# BPW5046-RGB-LED-Panel.net
KiCad netlist of a schematic drawn in EAGLE
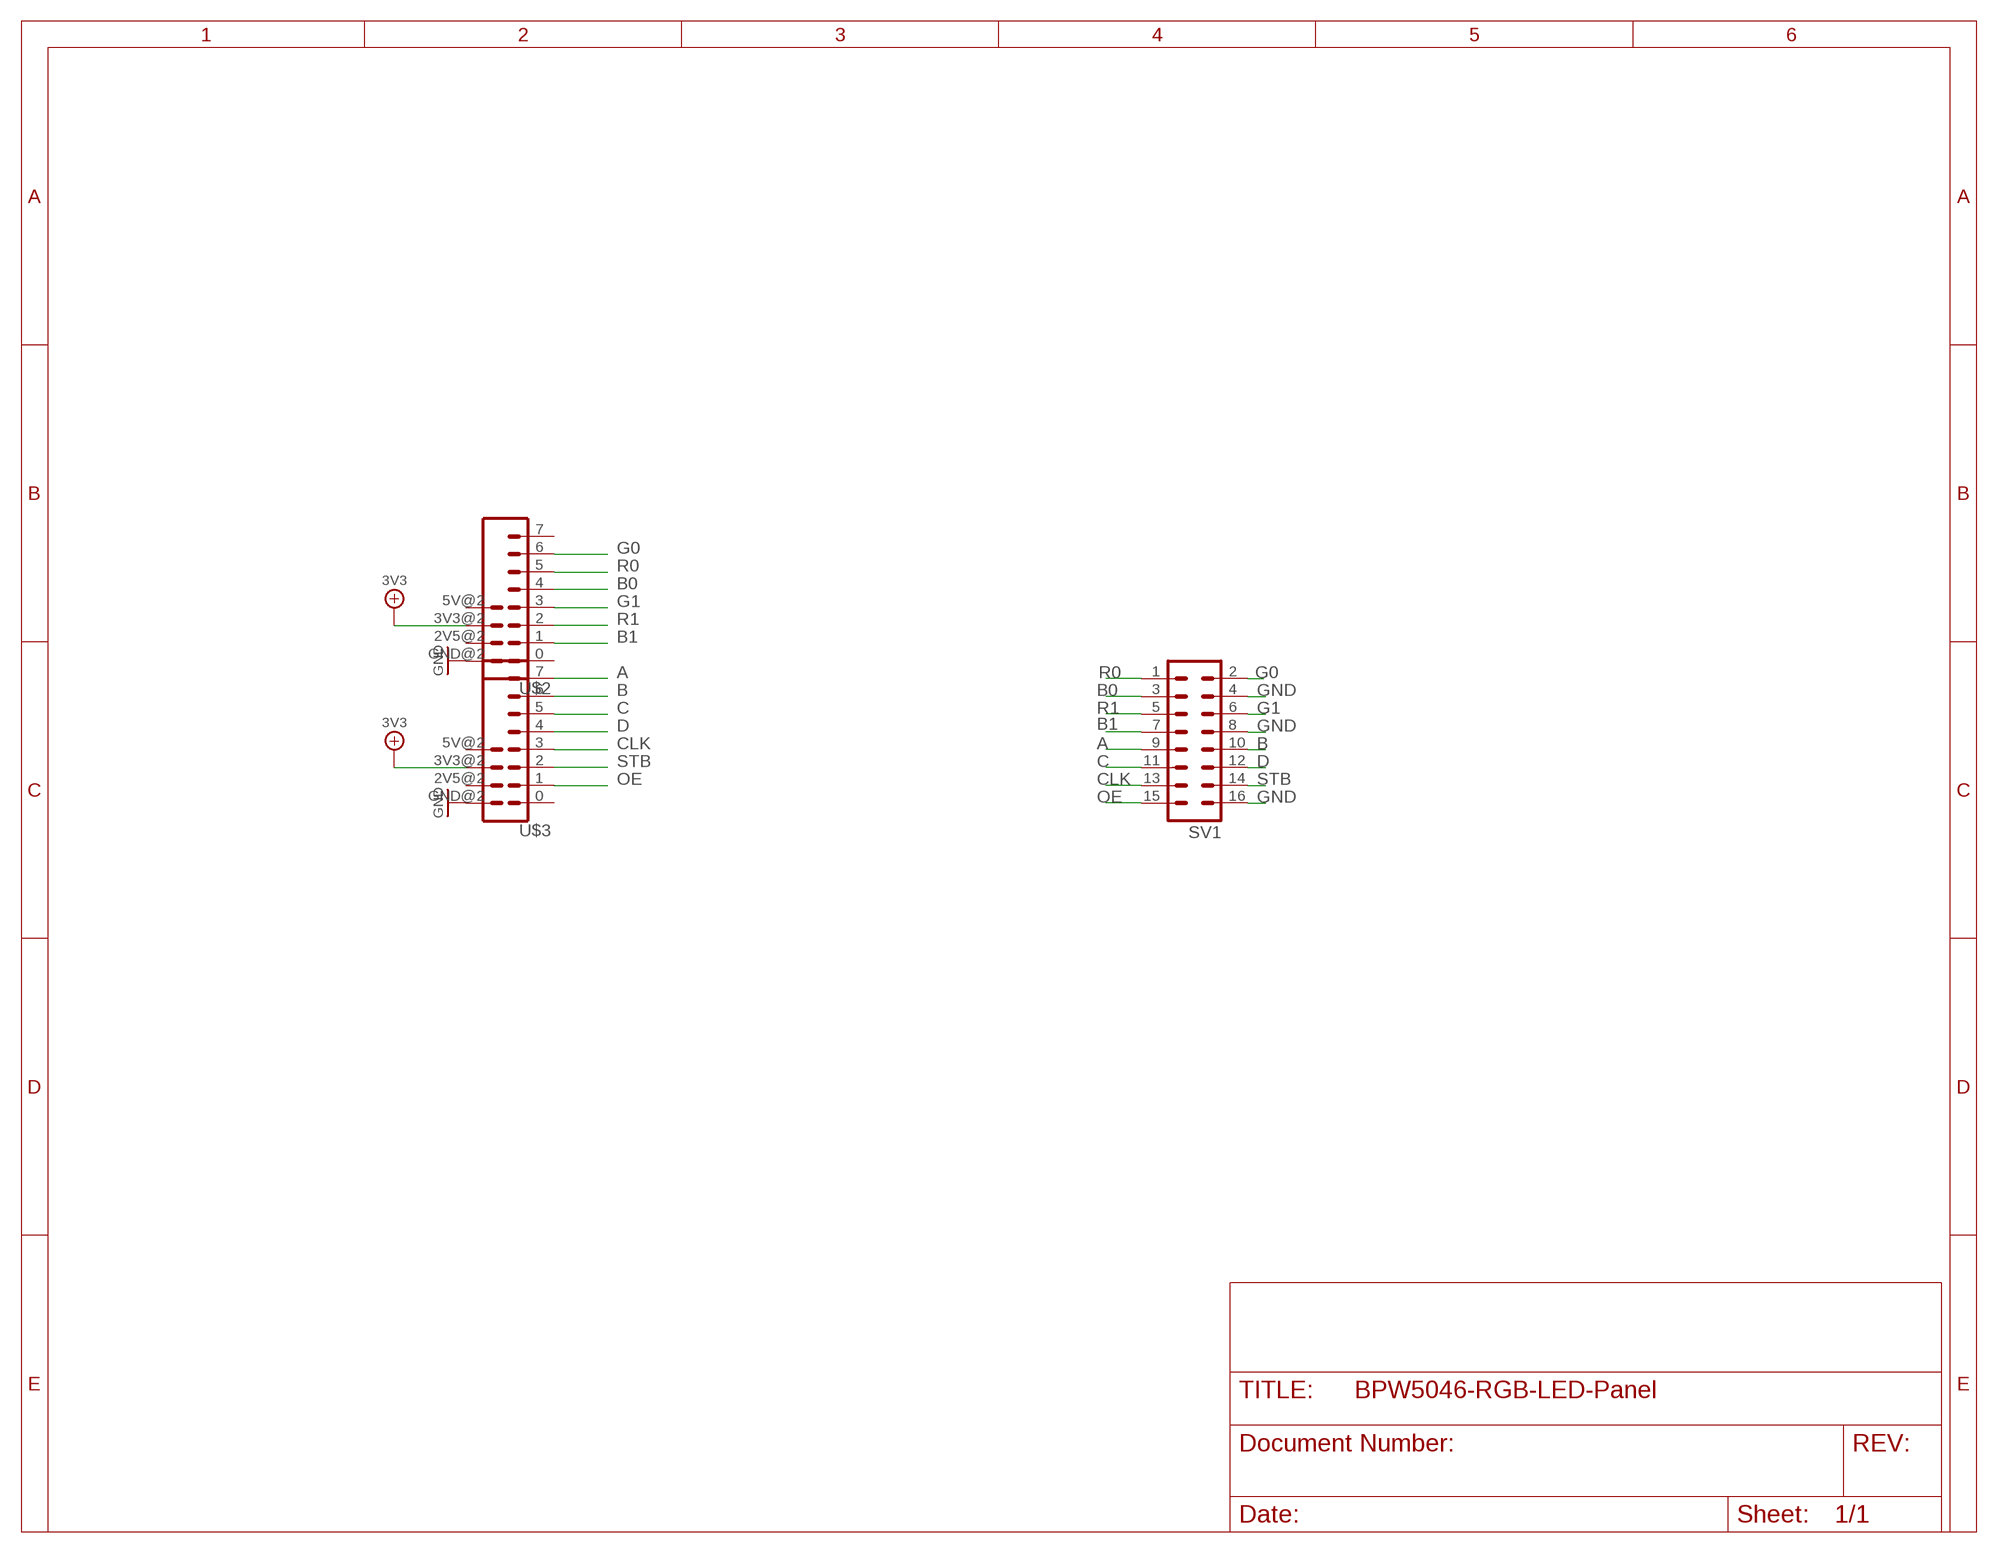
[diagram p0: schematic, sheet 1]

(export (version "E")
  (design (tool "Eeschema 10.0.6"))
  (components
    (comp (ref "SV1")
      (value "ML16")
      (footprint "eagle-import:ML16")
      (fields (field (name "PARTNO") "PRPC004DAAN-RC"))
      (libsource (lib "eagle-import") (part "ML16"))
    )
    (comp (ref "U$2")
      (value "WING8WING8_NOHOLES")
      (footprint "eagle-import:WINGSIDE_8BIT_NOHOLES")
      (fields (field (name "PARTNO") "68001-112HLF"))
      (libsource (lib "eagle-import") (part "WING8WING8_NOHOLES"))
    )
    (comp (ref "U$3")
      (value "WING8WING8_NOHOLES")
      (footprint "eagle-import:WINGSIDE_8BIT_NOHOLES")
      (fields (field (name "PARTNO") "68001-112HLF"))
      (libsource (lib "eagle-import") (part "WING8WING8_NOHOLES"))
    )
  )
  (nets
    (net (code "1") (name "/A") (class "Default")
      (node (ref "SV1") (pin "9") (pinfunction "9_9") (pintype "passive"))
      (node (ref "U$3") (pin "7") (pinfunction "8_7") (pintype "passive"))
    )
    (net (code "2") (name "/B") (class "Default")
      (node (ref "SV1") (pin "10") (pinfunction "10_10") (pintype "passive"))
      (node (ref "U$3") (pin "6") (pinfunction "7_6") (pintype "passive"))
    )
    (net (code "3") (name "/B0") (class "Default")
      (node (ref "SV1") (pin "3") (pinfunction "3_3") (pintype "passive"))
      (node (ref "U$2") (pin "4") (pinfunction "5_4") (pintype "passive"))
    )
    (net (code "4") (name "/B1") (class "Default")
      (node (ref "SV1") (pin "7") (pinfunction "7_7") (pintype "passive"))
      (node (ref "U$2") (pin "1") (pinfunction "2_1") (pintype "passive"))
    )
    (net (code "5") (name "/C") (class "Default")
      (node (ref "SV1") (pin "11") (pinfunction "11_11") (pintype "passive"))
      (node (ref "U$3") (pin "5") (pinfunction "6_5") (pintype "passive"))
    )
    (net (code "6") (name "/CLK") (class "Default")
      (node (ref "SV1") (pin "13") (pinfunction "13_13") (pintype "passive"))
      (node (ref "U$3") (pin "3") (pinfunction "4_3") (pintype "passive"))
    )
    (net (code "7") (name "/D") (class "Default")
      (node (ref "SV1") (pin "12") (pinfunction "12_12") (pintype "passive"))
      (node (ref "U$3") (pin "4") (pinfunction "5_4") (pintype "passive"))
    )
    (net (code "8") (name "/G0") (class "Default")
      (node (ref "SV1") (pin "2") (pinfunction "2_2") (pintype "passive"))
      (node (ref "U$2") (pin "6") (pinfunction "7_6") (pintype "passive"))
    )
    (net (code "9") (name "/G1") (class "Default")
      (node (ref "SV1") (pin "6") (pinfunction "6_6") (pintype "passive"))
      (node (ref "U$2") (pin "3") (pinfunction "4_3") (pintype "passive"))
    )
    (net (code "10") (name "/OE") (class "Default")
      (node (ref "SV1") (pin "15") (pinfunction "15_15") (pintype "passive"))
      (node (ref "U$3") (pin "1") (pinfunction "2_1") (pintype "passive"))
    )
    (net (code "11") (name "/R0") (class "Default")
      (node (ref "SV1") (pin "1") (pinfunction "1_1") (pintype "passive"))
      (node (ref "U$2") (pin "5") (pinfunction "6_5") (pintype "passive"))
    )
    (net (code "12") (name "/R1") (class "Default")
      (node (ref "SV1") (pin "5") (pinfunction "5_5") (pintype "passive"))
      (node (ref "U$2") (pin "2") (pinfunction "3_2") (pintype "passive"))
    )
    (net (code "13") (name "/STB") (class "Default")
      (node (ref "SV1") (pin "14") (pinfunction "14_14") (pintype "passive"))
      (node (ref "U$3") (pin "2") (pinfunction "3_2") (pintype "passive"))
    )
    (net (code "14") (name "3V3") (class "Default")
      (node (ref "U$2") (pin "3V3@2") (pinfunction "3V3_3V3@2") (pintype "passive"))
      (node (ref "U$3") (pin "3V3@2") (pinfunction "3V3_3V3@2") (pintype "passive"))
    )
    (net (code "15") (name "GND") (class "Default")
      (node (ref "SV1") (pin "16") (pinfunction "16_16") (pintype "passive"))
      (node (ref "SV1") (pin "4") (pinfunction "4_4") (pintype "passive"))
      (node (ref "SV1") (pin "8") (pinfunction "8_8") (pintype "passive"))
      (node (ref "U$2") (pin "GND@2") (pinfunction "GND_GND@2") (pintype "passive"))
      (node (ref "U$3") (pin "GND@2") (pinfunction "GND_GND@2") (pintype "passive"))
    )
    (net (code "16") (name "unconnected-(U$2-1-Pad0)") (class "Default")
      (node (ref "U$2") (pin "0") (pinfunction "1_0") (pintype "passive"))
    )
    (net (code "17") (name "unconnected-(U$2-2V5-Pad2V5@2)") (class "Default")
      (node (ref "U$2") (pin "2V5@2") (pinfunction "2V5_2V5@2") (pintype "passive"))
    )
    (net (code "18") (name "unconnected-(U$2-5V-Pad5V@2)") (class "Default")
      (node (ref "U$2") (pin "5V@2") (pinfunction "5V_5V@2") (pintype "passive"))
    )
    (net (code "19") (name "unconnected-(U$2-8-Pad7)") (class "Default")
      (node (ref "U$2") (pin "7") (pinfunction "8_7") (pintype "passive"))
    )
    (net (code "20") (name "unconnected-(U$3-1-Pad0)") (class "Default")
      (node (ref "U$3") (pin "0") (pinfunction "1_0") (pintype "passive"))
    )
    (net (code "21") (name "unconnected-(U$3-2V5-Pad2V5@2)") (class "Default")
      (node (ref "U$3") (pin "2V5@2") (pinfunction "2V5_2V5@2") (pintype "passive"))
    )
    (net (code "22") (name "unconnected-(U$3-5V-Pad5V@2)") (class "Default")
      (node (ref "U$3") (pin "5V@2") (pinfunction "5V_5V@2") (pintype "passive"))
    )
  )
)
